# MMA8652FCR1.net
KiCad netlist of a schematic drawn in Altium Designer
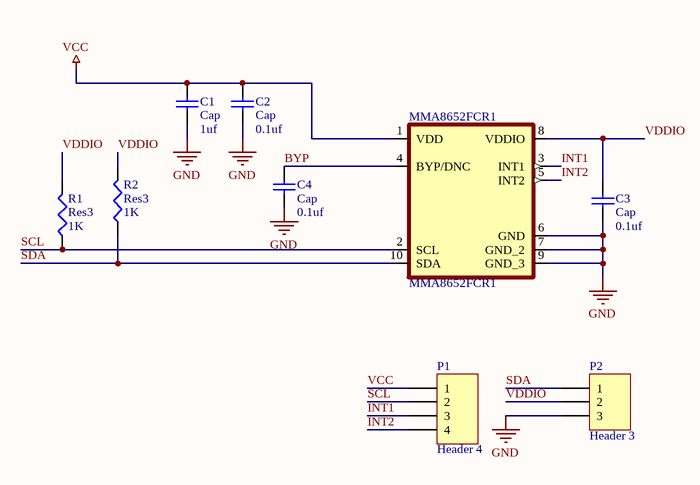
[diagram p0: MMA8652FCR1.SchDoc]

(export (version "E")
  (design (tool "Eeschema 10.0.6"))
  (components
    (comp (ref "C1")
      (value "Cap")
      (footprint "capacitor_10uf")
      (description "Capacitor")
      (fields (field (name "ALTIUM_VALUE") "1uf") (field (name "PUBLISHER") "Altium Limited"))
      (libsource (lib "Miscellaneous Devices") (part "Cap"))
    )
    (comp (ref "C2")
      (value "Cap")
      (footprint "capacitor_10uf")
      (description "Capacitor")
      (fields (field (name "ALTIUM_VALUE") "0.1uf") (field (name "PUBLISHER") "Altium Limited"))
      (libsource (lib "Miscellaneous Devices") (part "Cap"))
    )
    (comp (ref "C3")
      (value "Cap")
      (footprint "Capacitor_100nf")
      (description "Capacitor")
      (fields (field (name "ALTIUM_VALUE") "0.1uf") (field (name "PUBLISHER") "Altium Limited"))
      (libsource (lib "Miscellaneous Devices") (part "Cap"))
    )
    (comp (ref "C4")
      (value "Cap")
      (footprint "capacitor_10uf")
      (description "Capacitor")
      (fields (field (name "ALTIUM_VALUE") "0.1uf") (field (name "PUBLISHER") "Altium Limited"))
      (libsource (lib "Miscellaneous Devices") (part "Cap"))
    )
    (comp (ref "MMA8652FCR1")
      (value "MMA8652FCR1")
      (footprint "MMA8652FCR1")
      (libsource (lib "Accelerometres") (part "MMA8652FCR1"))
    )
    (comp (ref "P1")
      (value "Header 4")
      (footprint "HDR1X4")
      (description "Header, 4-Pin")
      (fields (field (name "PUBLISHER") "Altium Limited"))
      (libsource (lib "Miscellaneous Connectors") (part "Header 4"))
    )
    (comp (ref "P2")
      (value "Header 3")
      (footprint "HDR1X3")
      (description "Header, 3-Pin")
      (fields (field (name "PUBLISHER") "Altium Limited"))
      (libsource (lib "Miscellaneous Connectors") (part "Header 3"))
    )
    (comp (ref "R1")
      (value "Res3")
      (footprint "J1-0603")
      (description "Resistor")
      (fields (field (name "ALTIUM_VALUE") "1K") (field (name "PUBLISHER") "Altium Limited"))
      (libsource (lib "Miscellaneous Devices") (part "Res3"))
    )
    (comp (ref "R2")
      (value "Res3")
      (footprint "J1-0603")
      (description "Resistor")
      (fields (field (name "ALTIUM_VALUE") "1K") (field (name "PUBLISHER") "Altium Limited"))
      (libsource (lib "Miscellaneous Devices") (part "Res3"))
    )
  )
  (nets
    (net (code "1") (name "/BYP") (class "Default")
      (node (ref "C4") (pin "2") (pinfunction "2_2") (pintype "passive"))
      (node (ref "MMA8652FCR1") (pin "4") (pinfunction "BYP/DNC_4") (pintype "passive"))
    )
    (net (code "2") (name "/INT1") (class "Default")
      (node (ref "MMA8652FCR1") (pin "3") (pinfunction "INT1_3") (pintype "output"))
      (node (ref "P1") (pin "3") (pinfunction "3_3") (pintype "passive"))
    )
    (net (code "3") (name "/INT2") (class "Default")
      (node (ref "MMA8652FCR1") (pin "5") (pinfunction "INT2_5") (pintype "output"))
      (node (ref "P1") (pin "4") (pinfunction "4_4") (pintype "passive"))
    )
    (net (code "4") (name "/SCL") (class "Default")
      (node (ref "MMA8652FCR1") (pin "2") (pinfunction "SCL_2") (pintype "passive"))
      (node (ref "P1") (pin "2") (pinfunction "2_2") (pintype "passive"))
      (node (ref "R1") (pin "1") (pinfunction "1_1") (pintype "passive"))
    )
    (net (code "5") (name "/SDA") (class "Default")
      (node (ref "MMA8652FCR1") (pin "10") (pinfunction "SDA_10") (pintype "bidirectional"))
      (node (ref "P2") (pin "1") (pinfunction "1_1") (pintype "passive"))
      (node (ref "R2") (pin "1") (pinfunction "1_1") (pintype "passive"))
    )
    (net (code "6") (name "/VDDIO") (class "Default")
      (node (ref "C3") (pin "2") (pinfunction "2_2") (pintype "passive"))
      (node (ref "MMA8652FCR1") (pin "8") (pinfunction "VDDIO_8") (pintype "power_in"))
      (node (ref "P2") (pin "2") (pinfunction "2_2") (pintype "passive"))
      (node (ref "R1") (pin "2") (pinfunction "2_2") (pintype "passive"))
      (node (ref "R2") (pin "2") (pinfunction "2_2") (pintype "passive"))
    )
    (net (code "7") (name "GND") (class "Default")
      (node (ref "C1") (pin "1") (pinfunction "1_1") (pintype "passive"))
      (node (ref "C2") (pin "1") (pinfunction "1_1") (pintype "passive"))
      (node (ref "C3") (pin "1") (pinfunction "1_1") (pintype "passive"))
      (node (ref "C4") (pin "1") (pinfunction "1_1") (pintype "passive"))
      (node (ref "MMA8652FCR1") (pin "6") (pinfunction "GND_6") (pintype "passive"))
      (node (ref "MMA8652FCR1") (pin "7") (pinfunction "GND_2_7") (pintype "passive"))
      (node (ref "MMA8652FCR1") (pin "9") (pinfunction "GND_3_9") (pintype "passive"))
      (node (ref "P2") (pin "3") (pinfunction "3_3") (pintype "passive"))
    )
    (net (code "8") (name "VCC") (class "Default")
      (node (ref "C1") (pin "2") (pinfunction "2_2") (pintype "passive"))
      (node (ref "C2") (pin "2") (pinfunction "2_2") (pintype "passive"))
      (node (ref "MMA8652FCR1") (pin "1") (pinfunction "VDD_1") (pintype "power_in"))
      (node (ref "P1") (pin "1") (pinfunction "1_1") (pintype "passive"))
    )
  )
)
